# 04_-_ETHERNET.net
KiCad netlist of a schematic drawn in Altium Designer
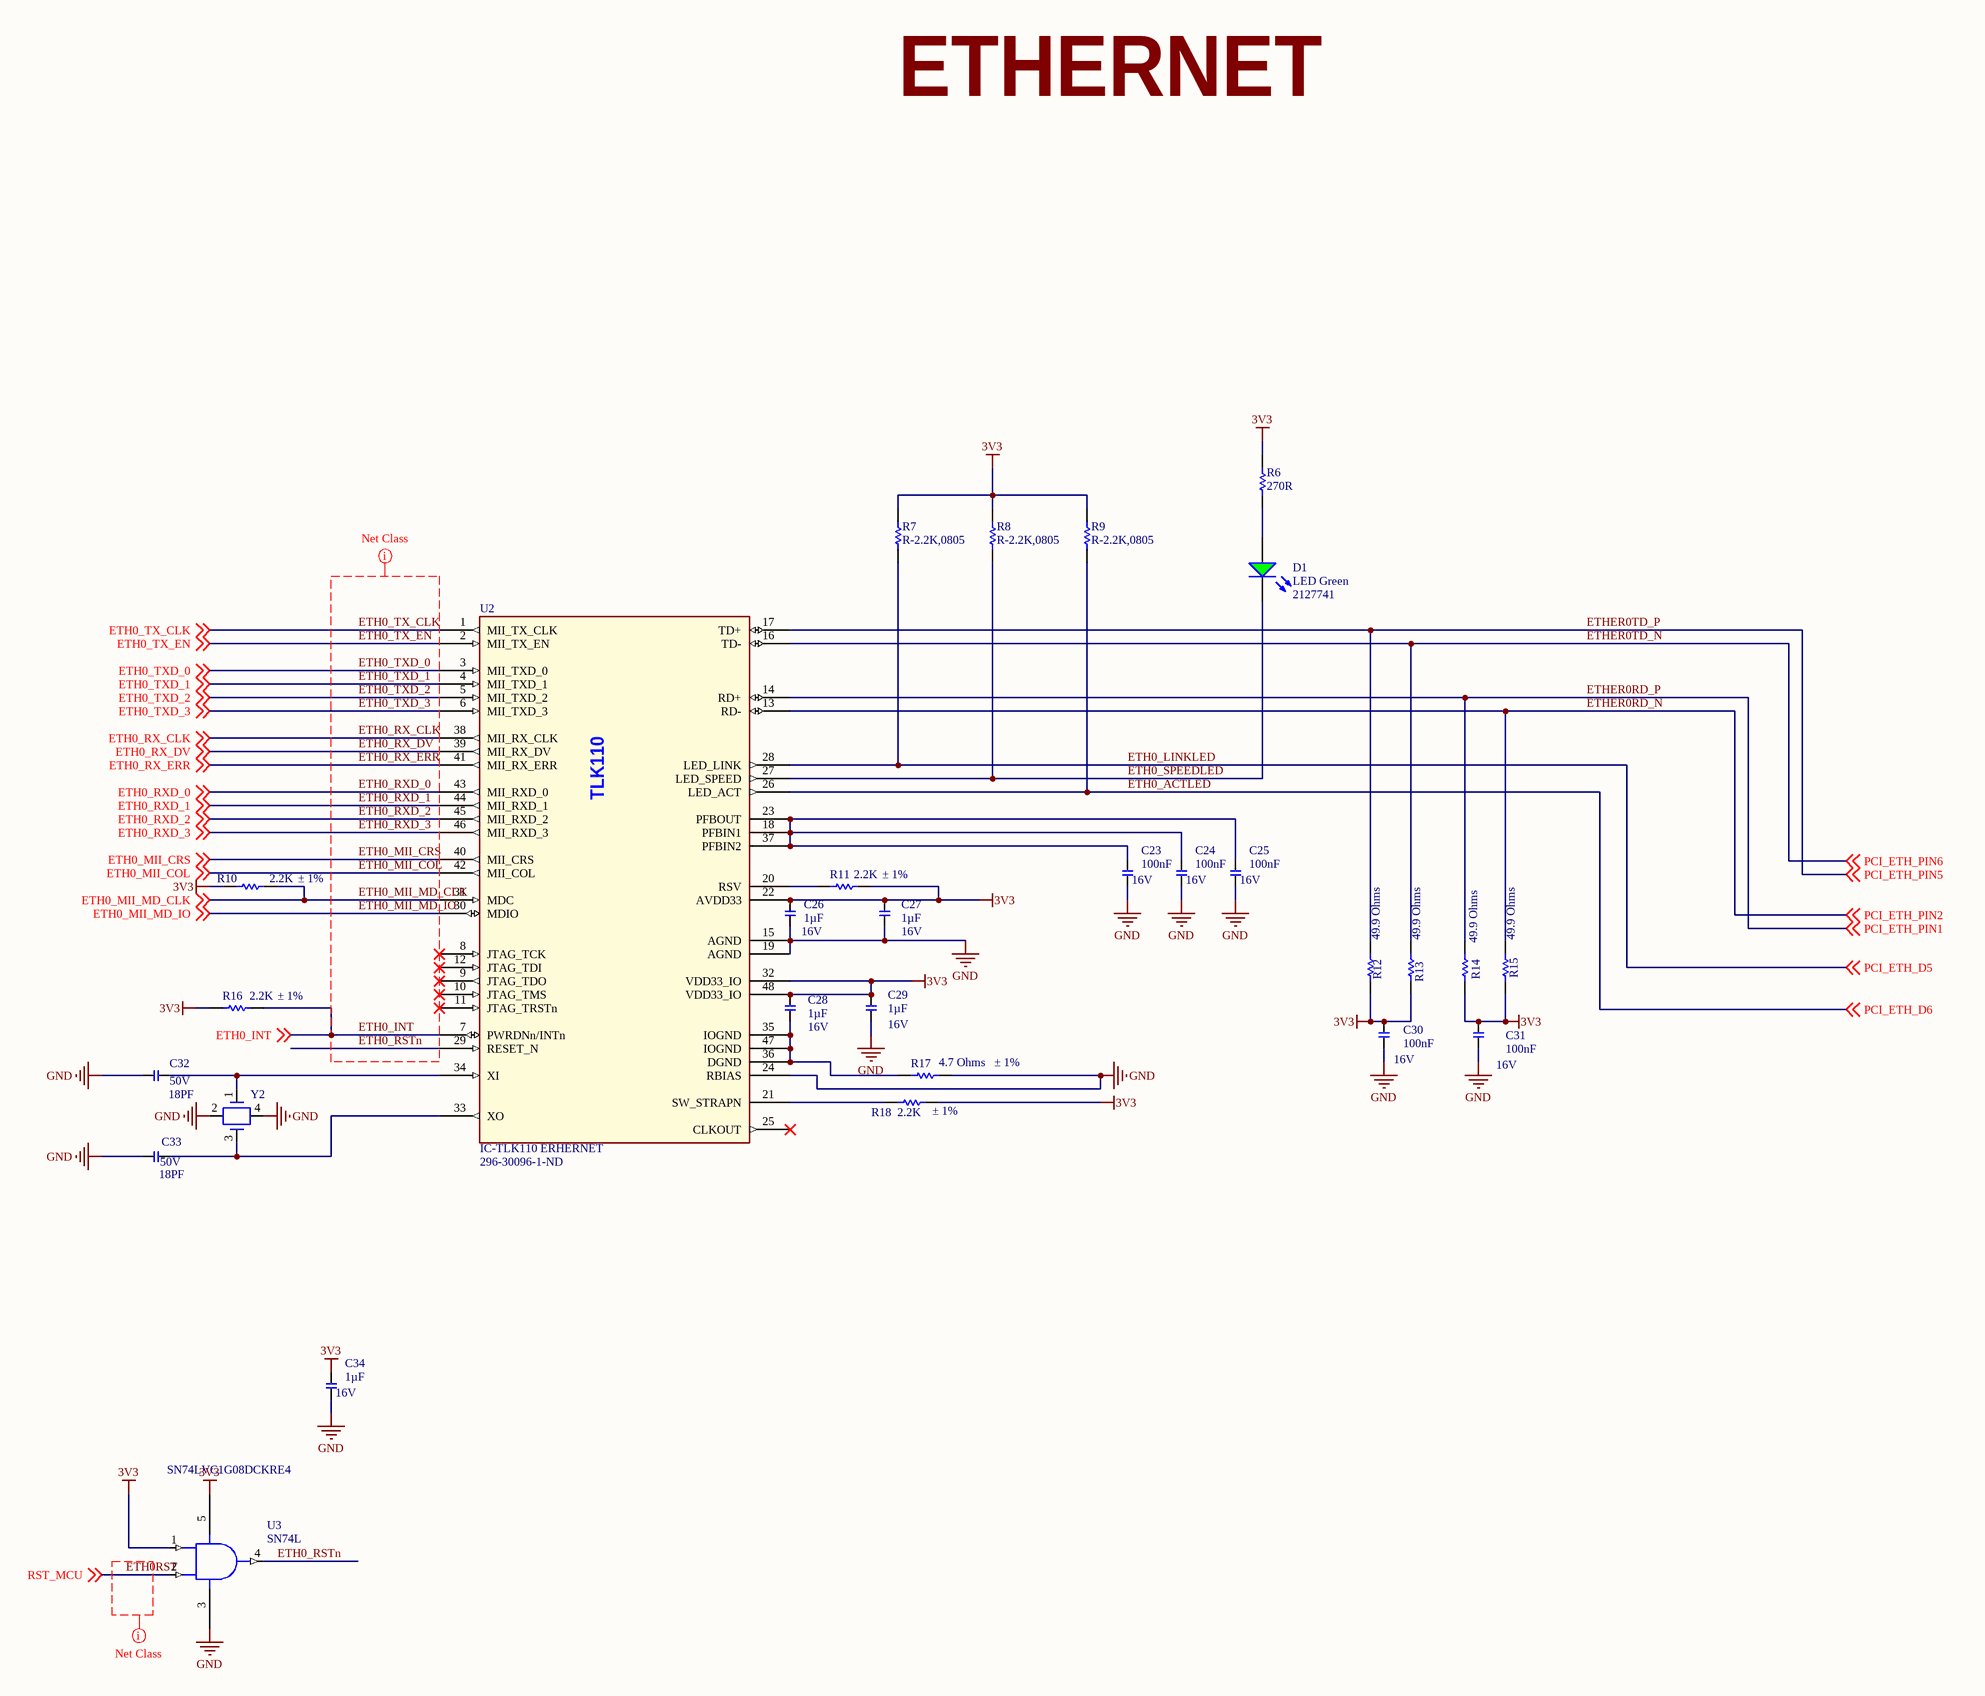
[diagram p0: [04] - ETHERNET.SchDoc]

(export (version "E")
  (design (tool "Eeschema 10.0.6"))
  (components
    (comp (ref "C23")
      (value "100nF")
      (footprint "C0805")
      (description "AVX - 0805YA103JAT2A - CAP, MLCC, C0G/NP0, 10NF, 16V, 0805")
      (fields
        (field (name "MANUFACTURER") "AVX")
        (field (name "MANUFACTURER PART NUMBER") "0805YA103JAT2A")
        (field (name "VOLTAGE - RATED") "16V")
      )
      (libsource (lib "CPU_STM_080816") (part "C-100NF,16V,0805"))
    )
    (comp (ref "C24")
      (value "100nF")
      (footprint "C0805")
      (description "AVX - 0805YA103JAT2A - CAP, MLCC, C0G/NP0, 10NF, 16V, 0805")
      (fields
        (field (name "MANUFACTURER") "AVX")
        (field (name "MANUFACTURER PART NUMBER") "0805YA103JAT2A")
        (field (name "VOLTAGE - RATED") "16V")
      )
      (libsource (lib "CPU_STM_080816") (part "C-100NF,16V,0805"))
    )
    (comp (ref "C25")
      (value "100nF")
      (footprint "C0805")
      (description "AVX - 0805YA103JAT2A - CAP, MLCC, C0G/NP0, 10NF, 16V, 0805")
      (fields
        (field (name "MANUFACTURER") "AVX")
        (field (name "MANUFACTURER PART NUMBER") "0805YA103JAT2A")
        (field (name "VOLTAGE - RATED") "16V")
      )
      (libsource (lib "CPU_STM_080816") (part "C-100NF,16V,0805"))
    )
    (comp (ref "C26")
      (value "1µF")
      (footprint "C0805")
      (description "AVX - 0805YC105KAT2A - CAP, MLCC, X7R, 1UF, 16V, 0805")
      (fields
        (field (name "MANUFACTURER") "AVX Corporation")
        (field (name "MANUFACTURER PART NUMBER") "0805YC105KAT2A")
        (field (name "VOLTAGE - RATED") "16V")
      )
      (libsource (lib "CPU_STM_080816") (part "C-1UF,16V,0805"))
    )
    (comp (ref "C27")
      (value "1µF")
      (footprint "C0805")
      (description "AVX - 0805YC105KAT2A - CAP, MLCC, X7R, 1UF, 16V, 0805")
      (fields
        (field (name "MANUFACTURER") "AVX Corporation")
        (field (name "MANUFACTURER PART NUMBER") "0805YC105KAT2A")
        (field (name "VOLTAGE - RATED") "16V")
      )
      (libsource (lib "CPU_STM_080816") (part "C-1UF,16V,0805"))
    )
    (comp (ref "C28")
      (value "1µF")
      (footprint "C0805")
      (description "AVX - 0805YC105KAT2A - CAP, MLCC, X7R, 1UF, 16V, 0805")
      (fields
        (field (name "MANUFACTURER") "AVX Corporation")
        (field (name "MANUFACTURER PART NUMBER") "0805YC105KAT2A")
        (field (name "VOLTAGE - RATED") "16V")
      )
      (libsource (lib "CPU_STM_080816") (part "C-1UF,16V,0805"))
    )
    (comp (ref "C29")
      (value "1µF")
      (footprint "C0805")
      (description "AVX - 0805YC105KAT2A - CAP, MLCC, X7R, 1UF, 16V, 0805")
      (fields
        (field (name "MANUFACTURER") "AVX Corporation")
        (field (name "MANUFACTURER PART NUMBER") "0805YC105KAT2A")
        (field (name "VOLTAGE - RATED") "16V")
      )
      (libsource (lib "CPU_STM_080816") (part "C-1UF,16V,0805"))
    )
    (comp (ref "C30")
      (value "100nF")
      (footprint "C0805")
      (description "AVX - 0805YA103JAT2A - CAP, MLCC, C0G/NP0, 10NF, 16V, 0805")
      (fields
        (field (name "MANUFACTURER") "AVX")
        (field (name "MANUFACTURER PART NUMBER") "0805YA103JAT2A")
        (field (name "VOLTAGE - RATED") "16V")
      )
      (libsource (lib "CPU_STM_080816") (part "C-100NF,16V,0805"))
    )
    (comp (ref "C31")
      (value "100nF")
      (footprint "C0805")
      (description "AVX - 0805YA103JAT2A - CAP, MLCC, C0G/NP0, 10NF, 16V, 0805")
      (fields
        (field (name "MANUFACTURER") "AVX")
        (field (name "MANUFACTURER PART NUMBER") "0805YA103JAT2A")
        (field (name "VOLTAGE - RATED") "16V")
      )
      (libsource (lib "CPU_STM_080816") (part "C-100NF,16V,0805"))
    )
    (comp (ref "C32")
      (value "18PF")
      (footprint "C0805")
      (description "MULTICOMP - MC0805N180J500CT - CAP, MLCC, C0G/NP0, 18PF, 50V,0805, REEL")
      (fields
        (field (name "MANUFACTURER") "Multicomp")
        (field (name "MANUFACTURER PART NUMBER") "MC0805N180J500CT")
        (field (name "VOLTAGE_RATING_DC") "50V")
      )
      (libsource (lib "CPU_STM_080816") (part "C-18PF,50V,0805"))
    )
    (comp (ref "C33")
      (value "18PF")
      (footprint "C0805")
      (description "MULTICOMP - MC0805N180J500CT - CAP, MLCC, C0G/NP0, 18PF, 50V,0805, REEL")
      (fields
        (field (name "MANUFACTURER") "Multicomp")
        (field (name "MANUFACTURER PART NUMBER") "MC0805N180J500CT")
        (field (name "VOLTAGE_RATING_DC") "50V")
      )
      (libsource (lib "CPU_STM_080816") (part "C-18PF,50V,0805"))
    )
    (comp (ref "C34")
      (value "1µF")
      (footprint "C0805")
      (description "AVX - 0805YC105KAT2A - CAP, MLCC, X7R, 1UF, 16V, 0805")
      (fields
        (field (name "MANUFACTURER") "AVX Corporation")
        (field (name "MANUFACTURER PART NUMBER") "0805YC105KAT2A")
        (field (name "VOLTAGE - RATED") "16V")
      )
      (libsource (lib "CPU_STM_080816") (part "C-1UF,16V,0805"))
    )
    (comp (ref "D1")
      (value "LED Green")
      (footprint "LED_0805")
      (description "LED Green SMD 20mA 2V 0805")
      (fields
        (field (name "TIINTPARTNUMBER") "1F0008")
        (field (name "MFR") "Dialight")
        (field (name "SUPPLIER PART NUMBER 1") "2127741")
      )
      (libsource (lib "CPU_STM_080816") (part "LED-Green SMD 20mA 2V 0805"))
    )
    (comp (ref "R6")
      (value "270R")
      (footprint "R0805")
      (description "TE CONNECTIVITY / NEOHM 270R Thin Film")
      (fields
        (field (name "MANUFACTURER") "TE CONNECTIVITY / NEOHM")
        (field (name "MANUFACTURER PART NUMBER") "CPF0805B270RE1")
      )
      (libsource (lib "CPU_STM_080816") (part "R-270R,0805"))
    )
    (comp (ref "R7")
      (value "R-2.2K,0805")
      (footprint "R0805")
      (description "PANASONIC - ERJP06F2201V - RESISTOR, THICK FILM, 2.2 KOHM, 0.5W, 1%")
      (fields
        (field (name "MANUFACTURER") "PANASONIC")
        (field (name "MANUFACTURER PART NUMBER") "ERJP06F2201V")
      )
      (libsource (lib "CPU_STM_080816") (part "R-2.2K,0805"))
    )
    (comp (ref "R8")
      (value "R-2.2K,0805")
      (footprint "R0805")
      (description "PANASONIC - ERJP06F2201V - RESISTOR, THICK FILM, 2.2 KOHM, 0.5W, 1%")
      (fields
        (field (name "MANUFACTURER") "PANASONIC")
        (field (name "MANUFACTURER PART NUMBER") "ERJP06F2201V")
      )
      (libsource (lib "CPU_STM_080816") (part "R-2.2K,0805"))
    )
    (comp (ref "R9")
      (value "R-2.2K,0805")
      (footprint "R0805")
      (description "PANASONIC - ERJP06F2201V - RESISTOR, THICK FILM, 2.2 KOHM, 0.5W, 1%")
      (fields
        (field (name "MANUFACTURER") "PANASONIC")
        (field (name "MANUFACTURER PART NUMBER") "ERJP06F2201V")
      )
      (libsource (lib "CPU_STM_080816") (part "R-2.2K,0805"))
    )
    (comp (ref "R10")
      (value "2.2K")
      (footprint "R0805")
      (description "PANASONIC - ERJP06F2201V - RESISTOR, THICK FILM, 2.2 KOHM, 0.5W, 1%")
      (fields
        (field (name "MANUFACTURER") "PANASONIC")
        (field (name "MANUFACTURER PART NUMBER") "ERJP06F2201V")
        (field (name "RESISTANCE TOLERANCE") "± 1%")
      )
      (libsource (lib "CPU_STM_080816") (part "R-2.2K,0805"))
    )
    (comp (ref "R11")
      (value "2.2K")
      (footprint "R0805")
      (description "PANASONIC - ERJP06F2201V - RESISTOR, THICK FILM, 2.2 KOHM, 0.5W, 1%")
      (fields
        (field (name "MANUFACTURER") "PANASONIC")
        (field (name "MANUFACTURER PART NUMBER") "ERJP06F2201V")
        (field (name "RESISTANCE TOLERANCE") "± 1%")
      )
      (libsource (lib "CPU_STM_080816") (part "R-2.2K,0805"))
    )
    (comp (ref "R12")
      (value "49.9 Ohms")
      (footprint "R0805")
      (description "PANASONIC - ERJP06F49R9V - RESISTOR, THICK FILM, 49.9 OHM, 0.5W, 1%")
      (fields
        (field (name "MANUFACTURER") "PANASONIC")
        (field (name "MANUFACTURER PART NUMBER") "ERJP06F49R9V")
      )
      (libsource (lib "CPU_STM_080816") (part "R-49.9R,0805"))
    )
    (comp (ref "R13")
      (value "49.9 Ohms")
      (footprint "R0805")
      (description "PANASONIC - ERJP06F49R9V - RESISTOR, THICK FILM, 49.9 OHM, 0.5W, 1%")
      (fields
        (field (name "MANUFACTURER") "PANASONIC")
        (field (name "MANUFACTURER PART NUMBER") "ERJP06F49R9V")
      )
      (libsource (lib "CPU_STM_080816") (part "R-49.9R,0805"))
    )
    (comp (ref "R14")
      (value "49.9 Ohms")
      (footprint "R0805")
      (description "PANASONIC - ERJP06F49R9V - RESISTOR, THICK FILM, 49.9 OHM, 0.5W, 1%")
      (fields
        (field (name "MANUFACTURER") "PANASONIC")
        (field (name "MANUFACTURER PART NUMBER") "ERJP06F49R9V")
      )
      (libsource (lib "CPU_STM_080816") (part "R-49.9R,0805"))
    )
    (comp (ref "R15")
      (value "49.9 Ohms")
      (footprint "R0805")
      (description "PANASONIC - ERJP06F49R9V - RESISTOR, THICK FILM, 49.9 OHM, 0.5W, 1%")
      (fields
        (field (name "MANUFACTURER") "PANASONIC")
        (field (name "MANUFACTURER PART NUMBER") "ERJP06F49R9V")
      )
      (libsource (lib "CPU_STM_080816") (part "R-49.9R,0805"))
    )
    (comp (ref "R16")
      (value "2.2K")
      (footprint "R0805")
      (description "PANASONIC - ERJP06F2201V - RESISTOR, THICK FILM, 2.2 KOHM, 0.5W, 1%")
      (fields
        (field (name "MANUFACTURER") "PANASONIC")
        (field (name "MANUFACTURER PART NUMBER") "ERJP06F2201V")
        (field (name "RESISTANCE TOLERANCE") "± 1%")
      )
      (libsource (lib "CPU_STM_080816") (part "R-2.2K,0805"))
    )
    (comp (ref "R17")
      (value "4.7 Ohms")
      (footprint "R0805")
      (description "BOURNS - CR0805-FX-4701GLF - RESISTOR, 4.7K, 0.125W, 1%")
      (fields
        (field (name "MANUFACTURER") "BOURNS")
        (field (name "MANUFACTURER PART NUMBER") "CR0805-FX-4701GLF")
        (field (name "RESISTANCE TOLERANCE") "± 1%")
      )
      (libsource (lib "CPU_STM_080816") (part "R-4.7K,0805"))
    )
    (comp (ref "R18")
      (value "2.2K")
      (footprint "R0805")
      (description "PANASONIC - ERJP06F2201V - RESISTOR, THICK FILM, 2.2 KOHM, 0.5W, 1%")
      (fields
        (field (name "MANUFACTURER") "PANASONIC")
        (field (name "MANUFACTURER PART NUMBER") "ERJP06F2201V")
        (field (name "RESISTANCE TOLERANCE") "± 1%")
      )
      (libsource (lib "CPU_STM_080816") (part "R-2.2K,0805"))
    )
    (comp (ref "U2")
      (value "IC-TLK110 ERHERNET")
      (footprint "STM-LQFP48_M")
      (description "IC ETHERNET PHY 10/100 48LQFP")
      (fields
        (field (name "SUPPLIER PART NUMBER 1") "296-30096-1-ND")
        (field (name "MANUFACTURER") "Texas Instruments")
        (field (name "MANUFACTURER PART NUMBER") "TLK110PTR")
      )
      (libsource (lib "CPU_STM_080816") (part "IC-TLK110 ERHERNET"))
    )
    (comp (ref "U3")
      (value "SN74L")
      (footprint "sm-so-sc70-5")
      (description "IC GATE AND 1CH 2-INP SC-70-5")
      (fields
        (field (name "MANUFACTURER") "Texas Instruments")
        (field (name "MANUFACTURER PART NUMBER") "SN74LVC1G08DCKRE4")
      )
      (libsource (lib "CPU_STM_080816") (part "IC-SN74LVC1G08DCKRE4- AND 1 CH"))
    )
    (comp (ref "Y2")
      (value "25MHz")
      (footprint "ABM8G")
      (description "RALTRON - RH100-25.000-18-F-3030-EXT - CRYSTAL, 25MHZ, 18PF, 3.2MM X 2.5MM")
      (fields
        (field (name "MANUFACTURER") "RALTRON")
        (field (name "MANUFACTURER PART NUMBER") "RH100-25.000-18-F-3030-EXT")
      )
      (libsource (lib "CPU_STM_080816") (part "OSC-Crystal25MHz-R"))
    )
  )
  (nets
    (net (code "1") (name "/ETH0_RSTn") (class "Default")
      (node (ref "U2") (pin "29") (pinfunction "RESET_N_29") (pintype "input"))
      (node (ref "U3") (pin "4") (pinfunction "Y_4") (pintype "output"))
    )
    (net (code "2") (name "/ETH0_SPEEDLED") (class "Default")
      (node (ref "D1") (pin "1") (pinfunction "K_1") (pintype "passive"))
      (node (ref "R8") (pin "1") (pinfunction "1_1") (pintype "passive"))
      (node (ref "U2") (pin "27") (pinfunction "LED_SPEED_27") (pintype "output"))
    )
    (net (code "3") (name "3V3") (class "Default")
      (node (ref "C26") (pin "2") (pinfunction "2_2") (pintype "passive"))
      (node (ref "C27") (pin "2") (pinfunction "2_2") (pintype "passive"))
      (node (ref "C28") (pin "2") (pinfunction "2_2") (pintype "passive"))
      (node (ref "C29") (pin "2") (pinfunction "2_2") (pintype "passive"))
      (node (ref "C30") (pin "2") (pinfunction "2_2") (pintype "passive"))
      (node (ref "C31") (pin "2") (pinfunction "2_2") (pintype "passive"))
      (node (ref "C34") (pin "2") (pinfunction "2_2") (pintype "passive"))
      (node (ref "R10") (pin "1") (pinfunction "1_1") (pintype "passive"))
      (node (ref "R11") (pin "2") (pinfunction "2_2") (pintype "passive"))
      (node (ref "R12") (pin "1") (pinfunction "1_1") (pintype "passive"))
      (node (ref "R13") (pin "1") (pinfunction "1_1") (pintype "passive"))
      (node (ref "R14") (pin "1") (pinfunction "1_1") (pintype "passive"))
      (node (ref "R15") (pin "1") (pinfunction "1_1") (pintype "passive"))
      (node (ref "R16") (pin "1") (pinfunction "1_1") (pintype "passive"))
      (node (ref "R18") (pin "2") (pinfunction "2_2") (pintype "passive"))
      (node (ref "R6") (pin "2") (pinfunction "2_2") (pintype "passive"))
      (node (ref "R7") (pin "2") (pinfunction "2_2") (pintype "passive"))
      (node (ref "R8") (pin "2") (pinfunction "2_2") (pintype "passive"))
      (node (ref "R9") (pin "2") (pinfunction "2_2") (pintype "passive"))
      (node (ref "U2") (pin "22") (pinfunction "AVDD33_22") (pintype "power_in"))
      (node (ref "U2") (pin "32") (pinfunction "VDD33_IO_32") (pintype "power_in"))
      (node (ref "U2") (pin "48") (pinfunction "VDD33_IO_48") (pintype "power_in"))
      (node (ref "U3") (pin "1") (pinfunction "A_1") (pintype "input"))
      (node (ref "U3") (pin "5") (pinfunction "VCC_5") (pintype "power_in"))
    )
    (net (code "4") (name "ETH0_INT") (class "Default")
      (node (ref "R16") (pin "2") (pinfunction "2_2") (pintype "passive"))
      (node (ref "U2") (pin "7") (pinfunction "PWRDNn/INTn_7") (pintype "bidirectional"))
    )
    (net (code "5") (name "ETH0_MII_COL") (class "Default")
      (node (ref "U2") (pin "42") (pinfunction "MII_COL_42") (pintype "output"))
    )
    (net (code "6") (name "ETH0_MII_CRS") (class "Default")
      (node (ref "U2") (pin "40") (pinfunction "MII_CRS_40") (pintype "output"))
    )
    (net (code "7") (name "ETH0_MII_MD_CLK") (class "Default")
      (node (ref "R10") (pin "2") (pinfunction "2_2") (pintype "passive"))
      (node (ref "U2") (pin "31") (pinfunction "MDC_31") (pintype "input"))
    )
    (net (code "8") (name "ETH0_MII_MD_IO") (class "Default")
      (node (ref "U2") (pin "30") (pinfunction "MDIO_30") (pintype "bidirectional"))
    )
    (net (code "9") (name "ETH0_RXD_0") (class "Default")
      (node (ref "U2") (pin "43") (pinfunction "MII_RXD_0_43") (pintype "output"))
    )
    (net (code "10") (name "ETH0_RXD_1") (class "Default")
      (node (ref "U2") (pin "44") (pinfunction "MII_RXD_1_44") (pintype "output"))
    )
    (net (code "11") (name "ETH0_RXD_2") (class "Default")
      (node (ref "U2") (pin "45") (pinfunction "MII_RXD_2_45") (pintype "output"))
    )
    (net (code "12") (name "ETH0_RXD_3") (class "Default")
      (node (ref "U2") (pin "46") (pinfunction "MII_RXD_3_46") (pintype "output"))
    )
    (net (code "13") (name "ETH0_RX_CLK") (class "Default")
      (node (ref "U2") (pin "38") (pinfunction "MII_RX_CLK_38") (pintype "output"))
    )
    (net (code "14") (name "ETH0_RX_DV") (class "Default")
      (node (ref "U2") (pin "39") (pinfunction "MII_RX_DV_39") (pintype "output"))
    )
    (net (code "15") (name "ETH0_RX_ERR") (class "Default")
      (node (ref "U2") (pin "41") (pinfunction "MII_RX_ERR_41") (pintype "output"))
    )
    (net (code "16") (name "ETH0_TXD_0") (class "Default")
      (node (ref "U2") (pin "3") (pinfunction "MII_TXD_0_3") (pintype "input"))
    )
    (net (code "17") (name "ETH0_TXD_1") (class "Default")
      (node (ref "U2") (pin "4") (pinfunction "MII_TXD_1_4") (pintype "input"))
    )
    (net (code "18") (name "ETH0_TXD_2") (class "Default")
      (node (ref "U2") (pin "5") (pinfunction "MII_TXD_2_5") (pintype "input"))
    )
    (net (code "19") (name "ETH0_TXD_3") (class "Default")
      (node (ref "U2") (pin "6") (pinfunction "MII_TXD_3_6") (pintype "input"))
    )
    (net (code "20") (name "ETH0_TX_CLK") (class "Default")
      (node (ref "U2") (pin "1") (pinfunction "MII_TX_CLK_1") (pintype "output"))
    )
    (net (code "21") (name "ETH0_TX_EN") (class "Default")
      (node (ref "U2") (pin "2") (pinfunction "MII_TX_EN_2") (pintype "input"))
    )
    (net (code "22") (name "GND") (class "Default")
      (node (ref "C23") (pin "1") (pinfunction "1_1") (pintype "passive"))
      (node (ref "C24") (pin "1") (pinfunction "1_1") (pintype "passive"))
      (node (ref "C25") (pin "1") (pinfunction "1_1") (pintype "passive"))
      (node (ref "C26") (pin "1") (pinfunction "1_1") (pintype "passive"))
      (node (ref "C27") (pin "1") (pinfunction "1_1") (pintype "passive"))
      (node (ref "C29") (pin "1") (pinfunction "1_1") (pintype "passive"))
      (node (ref "C30") (pin "1") (pinfunction "1_1") (pintype "passive"))
      (node (ref "C31") (pin "1") (pinfunction "1_1") (pintype "passive"))
      (node (ref "C32") (pin "1") (pinfunction "1_1") (pintype "passive"))
      (node (ref "C33") (pin "1") (pinfunction "1_1") (pintype "passive"))
      (node (ref "C34") (pin "1") (pinfunction "1_1") (pintype "passive"))
      (node (ref "R17") (pin "1") (pinfunction "1_1") (pintype "passive"))
      (node (ref "U2") (pin "15") (pinfunction "AGND_15") (pintype "power_in"))
      (node (ref "U2") (pin "19") (pinfunction "AGND_19") (pintype "power_in"))
      (node (ref "U2") (pin "24") (pinfunction "RBIAS_24") (pintype "passive"))
      (node (ref "U3") (pin "3") (pinfunction "GND_3") (pintype "power_in"))
      (node (ref "Y2") (pin "2") (pinfunction "2_2") (pintype "passive"))
      (node (ref "Y2") (pin "4") (pinfunction "4_4") (pintype "passive"))
    )
    (net (code "23") (name "Net-(D1-A)") (class "Default")
      (node (ref "D1") (pin "2") (pinfunction "A_2") (pintype "passive"))
      (node (ref "R6") (pin "1") (pinfunction "1_1") (pintype "passive"))
    )
    (net (code "24") (name "Net-(U2-DGND)") (class "Default")
      (node (ref "C28") (pin "1") (pinfunction "1_1") (pintype "passive"))
      (node (ref "R17") (pin "2") (pinfunction "2_2") (pintype "passive"))
      (node (ref "U2") (pin "35") (pinfunction "IOGND_35") (pintype "power_in"))
      (node (ref "U2") (pin "36") (pinfunction "DGND_36") (pintype "power_in"))
      (node (ref "U2") (pin "47") (pinfunction "IOGND_47") (pintype "power_in"))
    )
    (net (code "25") (name "Net-(U2-PFBIN1)") (class "Default")
      (node (ref "C23") (pin "2") (pinfunction "2_2") (pintype "passive"))
      (node (ref "C24") (pin "2") (pinfunction "2_2") (pintype "passive"))
      (node (ref "C25") (pin "2") (pinfunction "2_2") (pintype "passive"))
      (node (ref "U2") (pin "18") (pinfunction "PFBIN1_18") (pintype "power_in"))
      (node (ref "U2") (pin "23") (pinfunction "PFBOUT_23") (pintype "power_in"))
      (node (ref "U2") (pin "37") (pinfunction "PFBIN2_37") (pintype "power_in"))
    )
    (net (code "26") (name "Net-(U2-RSV)") (class "Default")
      (node (ref "R11") (pin "1") (pinfunction "1_1") (pintype "passive"))
      (node (ref "U2") (pin "20") (pinfunction "RSV_20") (pintype "passive"))
    )
    (net (code "27") (name "Net-(U2-SW_STRAPN)") (class "Default")
      (node (ref "R18") (pin "1") (pinfunction "1_1") (pintype "passive"))
      (node (ref "U2") (pin "21") (pinfunction "SW_STRAPN_21") (pintype "passive"))
    )
    (net (code "28") (name "Net-(U2-XI)") (class "Default")
      (node (ref "C32") (pin "2") (pinfunction "2_2") (pintype "passive"))
      (node (ref "U2") (pin "34") (pinfunction "XI_34") (pintype "input"))
      (node (ref "Y2") (pin "1") (pinfunction "1_1") (pintype "passive"))
    )
    (net (code "29") (name "Net-(U2-XO)") (class "Default")
      (node (ref "C33") (pin "2") (pinfunction "2_2") (pintype "passive"))
      (node (ref "U2") (pin "33") (pinfunction "XO_33") (pintype "output"))
      (node (ref "Y2") (pin "3") (pinfunction "3_3") (pintype "passive"))
    )
    (net (code "30") (name "PCI_ETH_D5") (class "Default")
      (node (ref "R7") (pin "1") (pinfunction "1_1") (pintype "passive"))
      (node (ref "U2") (pin "28") (pinfunction "LED_LINK_28") (pintype "output"))
    )
    (net (code "31") (name "PCI_ETH_D6") (class "Default")
      (node (ref "R9") (pin "1") (pinfunction "1_1") (pintype "passive"))
      (node (ref "U2") (pin "26") (pinfunction "LED_ACT_26") (pintype "output"))
    )
    (net (code "32") (name "PCI_ETH_PIN1") (class "Default")
      (node (ref "R14") (pin "2") (pinfunction "2_2") (pintype "passive"))
      (node (ref "U2") (pin "14") (pinfunction "RD+_14") (pintype "bidirectional"))
    )
    (net (code "33") (name "PCI_ETH_PIN2") (class "Default")
      (node (ref "R15") (pin "2") (pinfunction "2_2") (pintype "passive"))
      (node (ref "U2") (pin "13") (pinfunction "RD-_13") (pintype "bidirectional"))
    )
    (net (code "34") (name "PCI_ETH_PIN5") (class "Default")
      (node (ref "R12") (pin "2") (pinfunction "2_2") (pintype "passive"))
      (node (ref "U2") (pin "17") (pinfunction "TD+_17") (pintype "bidirectional"))
    )
    (net (code "35") (name "PCI_ETH_PIN6") (class "Default")
      (node (ref "R13") (pin "2") (pinfunction "2_2") (pintype "passive"))
      (node (ref "U2") (pin "16") (pinfunction "TD-_16") (pintype "bidirectional"))
    )
    (net (code "36") (name "RST_MCU") (class "Default")
      (node (ref "U3") (pin "2") (pinfunction "B_2") (pintype "input"))
    )
    (net (code "37") (name "unconnected-(U2-CLKOUT-Pad25)") (class "Default")
      (node (ref "U2") (pin "25") (pinfunction "CLKOUT_25") (pintype "output+no_connect"))
    )
    (net (code "38") (name "unconnected-(U2-JTAG_TCK-Pad8)") (class "Default")
      (node (ref "U2") (pin "8") (pinfunction "JTAG_TCK_8") (pintype "input+no_connect"))
    )
    (net (code "39") (name "unconnected-(U2-JTAG_TDI-Pad12)") (class "Default")
      (node (ref "U2") (pin "12") (pinfunction "JTAG_TDI_12") (pintype "input+no_connect"))
    )
    (net (code "40") (name "unconnected-(U2-JTAG_TDO-Pad9)") (class "Default")
      (node (ref "U2") (pin "9") (pinfunction "JTAG_TDO_9") (pintype "output+no_connect"))
    )
    (net (code "41") (name "unconnected-(U2-JTAG_TMS-Pad10)") (class "Default")
      (node (ref "U2") (pin "10") (pinfunction "JTAG_TMS_10") (pintype "input+no_connect"))
    )
    (net (code "42") (name "unconnected-(U2-JTAG_TRSTn-Pad11)") (class "Default")
      (node (ref "U2") (pin "11") (pinfunction "JTAG_TRSTn_11") (pintype "input+no_connect"))
    )
  )
)
